# Schatten5.net
KiCad netlist of a schematic drawn in EAGLE
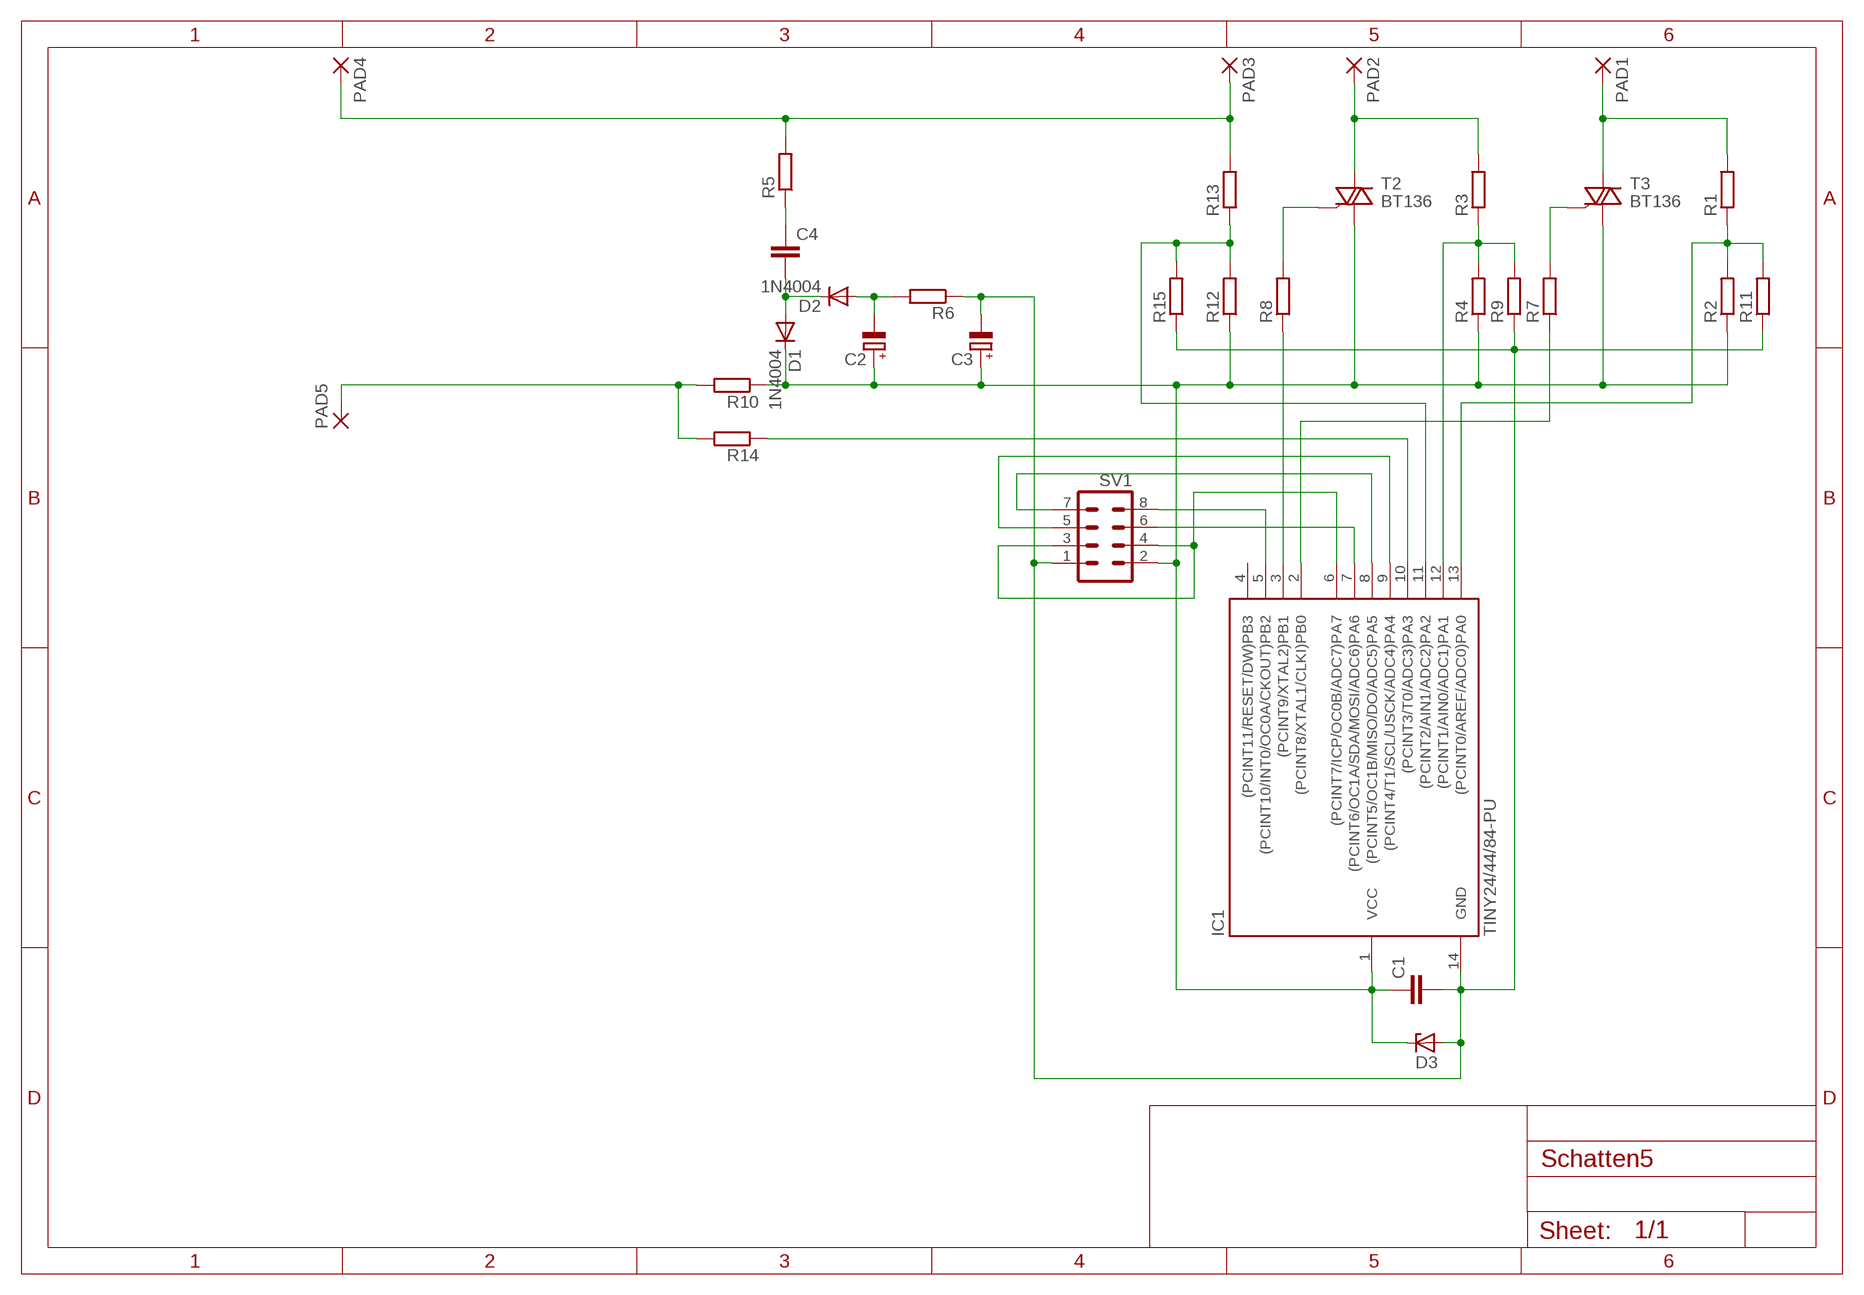
[diagram p0: schematic, sheet 1]

(export (version "E")
  (design (tool "Eeschema 10.0.6"))
  (components
    (comp (ref "C1")
      (value "C-EUC3225")
      (footprint "eagle-import:C3225")
      (libsource (lib "eagle-import") (part "C-EUC3225"))
    )
    (comp (ref "C2")
      (value "CPOL-EUE5-8.5")
      (footprint "eagle-import:E5-8,5")
      (libsource (lib "eagle-import") (part "CPOL-EUE5-8.5"))
    )
    (comp (ref "C3")
      (value "CPOL-EUE5-8.5")
      (footprint "eagle-import:E5-8,5")
      (libsource (lib "eagle-import") (part "CPOL-EUE5-8.5"))
    )
    (comp (ref "C4")
      (value "C-EU150-064X183")
      (footprint "eagle-import:C150-064X183")
      (libsource (lib "eagle-import") (part "C-EU150-064X183"))
    )
    (comp (ref "D1")
      (value "1N4004")
      (footprint "eagle-import:DO41-10")
      (libsource (lib "eagle-import") (part "1N4004"))
    )
    (comp (ref "D2")
      (value "1N4004")
      (footprint "eagle-import:DO41-10")
      (libsource (lib "eagle-import") (part "1N4004"))
    )
    (comp (ref "D3")
      (value "ZENER-DIODEZD-7.5")
      (footprint "eagle-import:ZDIO-7.5")
      (libsource (lib "eagle-import") (part "ZENER-DIODEZD-7.5"))
    )
    (comp (ref "IC1")
      (value "TINY24/44/84-PU")
      (footprint "eagle-import:DIL14")
      (libsource (lib "eagle-import") (part "TINY24/44/84-PU"))
    )
    (comp (ref "PAD1")
      (value "1,6/0,9")
      (footprint "eagle-import:1,6_0,9")
      (libsource (lib "eagle-import") (part "1,6/0,9"))
    )
    (comp (ref "PAD2")
      (value "1,6/0,9")
      (footprint "eagle-import:1,6_0,9")
      (libsource (lib "eagle-import") (part "1,6/0,9"))
    )
    (comp (ref "PAD3")
      (value "1,6/0,9")
      (footprint "eagle-import:1,6_0,9")
      (libsource (lib "eagle-import") (part "1,6/0,9"))
    )
    (comp (ref "PAD4")
      (value "1,6/0,9")
      (footprint "eagle-import:1,6_0,9")
      (libsource (lib "eagle-import") (part "1,6/0,9"))
    )
    (comp (ref "PAD5")
      (value "1,6/0,9")
      (footprint "eagle-import:1,6_0,9")
      (libsource (lib "eagle-import") (part "1,6/0,9"))
    )
    (comp (ref "R1")
      (value "R-EU_0207/10")
      (footprint "eagle-import:0207_10")
      (libsource (lib "eagle-import") (part "R-EU_0207/10"))
    )
    (comp (ref "R2")
      (value "R-EU_0207/10")
      (footprint "eagle-import:0207_10")
      (libsource (lib "eagle-import") (part "R-EU_0207/10"))
    )
    (comp (ref "R3")
      (value "R-EU_0207/10")
      (footprint "eagle-import:0207_10")
      (libsource (lib "eagle-import") (part "R-EU_0207/10"))
    )
    (comp (ref "R4")
      (value "R-EU_0207/10")
      (footprint "eagle-import:0207_10")
      (libsource (lib "eagle-import") (part "R-EU_0207/10"))
    )
    (comp (ref "R5")
      (value "R-EU_0207/10")
      (footprint "eagle-import:0207_10")
      (libsource (lib "eagle-import") (part "R-EU_0207/10"))
    )
    (comp (ref "R6")
      (value "R-EU_0207/10")
      (footprint "eagle-import:0207_10")
      (libsource (lib "eagle-import") (part "R-EU_0207/10"))
    )
    (comp (ref "R7")
      (value "R-EU_0207/10")
      (footprint "eagle-import:0207_10")
      (libsource (lib "eagle-import") (part "R-EU_0207/10"))
    )
    (comp (ref "R8")
      (value "R-EU_0207/10")
      (footprint "eagle-import:0207_10")
      (libsource (lib "eagle-import") (part "R-EU_0207/10"))
    )
    (comp (ref "R9")
      (value "R-EU_0207/10")
      (footprint "eagle-import:0207_10")
      (libsource (lib "eagle-import") (part "R-EU_0207/10"))
    )
    (comp (ref "R10")
      (value "R-EU_0207/10")
      (footprint "eagle-import:0207_10")
      (libsource (lib "eagle-import") (part "R-EU_0207/10"))
    )
    (comp (ref "R11")
      (value "R-EU_0207/10")
      (footprint "eagle-import:0207_10")
      (libsource (lib "eagle-import") (part "R-EU_0207/10"))
    )
    (comp (ref "R12")
      (value "R-EU_0207/10")
      (footprint "eagle-import:0207_10")
      (libsource (lib "eagle-import") (part "R-EU_0207/10"))
    )
    (comp (ref "R13")
      (value "R-EU_0207/10")
      (footprint "eagle-import:0207_10")
      (libsource (lib "eagle-import") (part "R-EU_0207/10"))
    )
    (comp (ref "R14")
      (value "R-EU_0207/10")
      (footprint "eagle-import:0207_10")
      (libsource (lib "eagle-import") (part "R-EU_0207/10"))
    )
    (comp (ref "R15")
      (value "R-EU_0207/10")
      (footprint "eagle-import:0207_10")
      (libsource (lib "eagle-import") (part "R-EU_0207/10"))
    )
    (comp (ref "SV1")
      (value "MA04-2")
      (footprint "eagle-import:MA04-2")
      (libsource (lib "eagle-import") (part "MA04-2"))
    )
    (comp (ref "T2")
      (value "BT136")
      (footprint "eagle-import:TO220AB")
      (libsource (lib "eagle-import") (part "BT136"))
    )
    (comp (ref "T3")
      (value "BT136")
      (footprint "eagle-import:TO220AB")
      (libsource (lib "eagle-import") (part "BT136"))
    )
  )
  (nets
    (net (code "1") (name "Net-(C2-Pad-)") (class "Default")
      (node (ref "C2") (pin "-") (pinfunction "-_-") (pintype "passive"))
      (node (ref "D2") (pin "A") (pinfunction "A_A") (pintype "passive"))
      (node (ref "R6") (pin "2") (pinfunction "2_2") (pintype "passive"))
    )
    (net (code "2") (name "Net-(C4-Pad1)") (class "Default")
      (node (ref "C4") (pin "1") (pinfunction "1_1") (pintype "passive"))
      (node (ref "R5") (pin "1") (pinfunction "1_1") (pintype "passive"))
    )
    (net (code "3") (name "Net-(C4-Pad2)") (class "Default")
      (node (ref "C4") (pin "2") (pinfunction "2_2") (pintype "passive"))
      (node (ref "D1") (pin "A") (pinfunction "A_A") (pintype "passive"))
      (node (ref "D2") (pin "C") (pinfunction "C_C") (pintype "passive"))
    )
    (net (code "4") (name "Net-(IC1-(PCINT0{slash}AREF{slash}ADC0)PA0)") (class "Default")
      (node (ref "IC1") (pin "13") (pinfunction "(PCINT0/AREF/ADC0)PA0_13") (pintype "bidirectional"))
      (node (ref "R1") (pin "1") (pinfunction "1_1") (pintype "passive"))
      (node (ref "R11") (pin "2") (pinfunction "2_2") (pintype "passive"))
      (node (ref "R2") (pin "2") (pinfunction "2_2") (pintype "passive"))
    )
    (net (code "5") (name "Net-(IC1-(PCINT1{slash}AIN0{slash}ADC1)PA1)") (class "Default")
      (node (ref "IC1") (pin "12") (pinfunction "(PCINT1/AIN0/ADC1)PA1_12") (pintype "bidirectional"))
      (node (ref "R3") (pin "1") (pinfunction "1_1") (pintype "passive"))
      (node (ref "R4") (pin "2") (pinfunction "2_2") (pintype "passive"))
      (node (ref "R9") (pin "2") (pinfunction "2_2") (pintype "passive"))
    )
    (net (code "6") (name "Net-(IC1-(PCINT2{slash}AIN1{slash}ADC2)PA2)") (class "Default")
      (node (ref "IC1") (pin "11") (pinfunction "(PCINT2/AIN1/ADC2)PA2_11") (pintype "bidirectional"))
      (node (ref "R12") (pin "2") (pinfunction "2_2") (pintype "passive"))
      (node (ref "R13") (pin "1") (pinfunction "1_1") (pintype "passive"))
      (node (ref "R15") (pin "2") (pinfunction "2_2") (pintype "passive"))
    )
    (net (code "7") (name "Net-(IC1-(PCINT3{slash}T0{slash}ADC3)PA3)") (class "Default")
      (node (ref "IC1") (pin "10") (pinfunction "(PCINT3/T0/ADC3)PA3_10") (pintype "bidirectional"))
      (node (ref "R14") (pin "1") (pinfunction "1_1") (pintype "passive"))
    )
    (net (code "8") (name "Net-(IC1-(PCINT4{slash}T1{slash}SCL{slash}USCK{slash}ADC4)PA4)") (class "Default")
      (node (ref "IC1") (pin "9") (pinfunction "(PCINT4/T1/SCL/USCK/ADC4)PA4_9") (pintype "bidirectional"))
      (node (ref "SV1") (pin "5") (pinfunction "5_5") (pintype "passive"))
    )
    (net (code "9") (name "Net-(IC1-(PCINT5{slash}OC1B{slash}MISO{slash}DO{slash}ADC5)PA5)") (class "Default")
      (node (ref "IC1") (pin "8") (pinfunction "(PCINT5/OC1B/MISO/DO/ADC5)PA5_8") (pintype "bidirectional"))
      (node (ref "SV1") (pin "7") (pinfunction "7_7") (pintype "passive"))
    )
    (net (code "10") (name "Net-(IC1-(PCINT6{slash}OC1A{slash}SDA{slash}MOSI{slash}ADC6)PA6)") (class "Default")
      (node (ref "IC1") (pin "7") (pinfunction "(PCINT6/OC1A/SDA/MOSI/ADC6)PA6_7") (pintype "bidirectional"))
      (node (ref "SV1") (pin "6") (pinfunction "6_6") (pintype "passive"))
    )
    (net (code "11") (name "Net-(IC1-(PCINT7{slash}ICP{slash}OC0B{slash}ADC7)PA7)") (class "Default")
      (node (ref "IC1") (pin "6") (pinfunction "(PCINT7/ICP/OC0B/ADC7)PA7_6") (pintype "bidirectional"))
      (node (ref "SV1") (pin "3") (pinfunction "3_3") (pintype "passive"))
      (node (ref "SV1") (pin "4") (pinfunction "4_4") (pintype "passive"))
    )
    (net (code "12") (name "Net-(IC1-(PCINT8{slash}XTAL1{slash}CLKI)PB0)") (class "Default")
      (node (ref "IC1") (pin "2") (pinfunction "(PCINT8/XTAL1/CLKI)PB0_2") (pintype "bidirectional"))
      (node (ref "R7") (pin "1") (pinfunction "1_1") (pintype "passive"))
    )
    (net (code "13") (name "Net-(IC1-(PCINT9{slash}XTAL2)PB1)") (class "Default")
      (node (ref "IC1") (pin "3") (pinfunction "(PCINT9/XTAL2)PB1_3") (pintype "bidirectional"))
      (node (ref "R8") (pin "1") (pinfunction "1_1") (pintype "passive"))
    )
    (net (code "14") (name "Net-(IC1-(PCINT10{slash}INT0{slash}OC0A{slash}CKOUT)PB2)") (class "Default")
      (node (ref "IC1") (pin "5") (pinfunction "(PCINT10/INT0/OC0A/CKOUT)PB2_5") (pintype "bidirectional"))
      (node (ref "SV1") (pin "8") (pinfunction "8_8") (pintype "passive"))
    )
    (net (code "15") (name "Net-(IC1-GND)") (class "Default")
      (node (ref "C1") (pin "2") (pinfunction "2_2") (pintype "passive"))
      (node (ref "C3") (pin "-") (pinfunction "-_-") (pintype "passive"))
      (node (ref "D3") (pin "A") (pinfunction "A_A") (pintype "passive"))
      (node (ref "IC1") (pin "14") (pinfunction "GND_14") (pintype "power_in"))
      (node (ref "R11") (pin "1") (pinfunction "1_1") (pintype "passive"))
      (node (ref "R15") (pin "1") (pinfunction "1_1") (pintype "passive"))
      (node (ref "R6") (pin "1") (pinfunction "1_1") (pintype "passive"))
      (node (ref "R9") (pin "1") (pinfunction "1_1") (pintype "passive"))
      (node (ref "SV1") (pin "1") (pinfunction "1_1") (pintype "passive"))
    )
    (net (code "16") (name "Net-(IC1-VCC)") (class "Default")
      (node (ref "C1") (pin "1") (pinfunction "1_1") (pintype "passive"))
      (node (ref "C2") (pin "+") (pinfunction "+_+") (pintype "passive"))
      (node (ref "C3") (pin "+") (pinfunction "+_+") (pintype "passive"))
      (node (ref "D1") (pin "C") (pinfunction "C_C") (pintype "passive"))
      (node (ref "D3") (pin "C") (pinfunction "C_C") (pintype "passive"))
      (node (ref "IC1") (pin "1") (pinfunction "VCC_1") (pintype "power_in"))
      (node (ref "R10") (pin "1") (pinfunction "1_1") (pintype "passive"))
      (node (ref "R12") (pin "1") (pinfunction "1_1") (pintype "passive"))
      (node (ref "R2") (pin "1") (pinfunction "1_1") (pintype "passive"))
      (node (ref "R4") (pin "1") (pinfunction "1_1") (pintype "passive"))
      (node (ref "SV1") (pin "2") (pinfunction "2_2") (pintype "passive"))
      (node (ref "T2") (pin "1") (pinfunction "A1_1") (pintype "passive"))
      (node (ref "T3") (pin "1") (pinfunction "A1_1") (pintype "passive"))
    )
    (net (code "17") (name "Net-(PAD1-P)") (class "Default")
      (node (ref "PAD1") (pin "1") (pinfunction "P_1") (pintype "passive"))
      (node (ref "R1") (pin "2") (pinfunction "2_2") (pintype "passive"))
      (node (ref "T3") (pin "2") (pinfunction "A2_2") (pintype "passive"))
    )
    (net (code "18") (name "Net-(PAD2-P)") (class "Default")
      (node (ref "PAD2") (pin "1") (pinfunction "P_1") (pintype "passive"))
      (node (ref "R3") (pin "2") (pinfunction "2_2") (pintype "passive"))
      (node (ref "T2") (pin "2") (pinfunction "A2_2") (pintype "passive"))
    )
    (net (code "19") (name "Net-(PAD3-P)") (class "Default")
      (node (ref "PAD3") (pin "1") (pinfunction "P_1") (pintype "passive"))
      (node (ref "PAD4") (pin "1") (pinfunction "P_1") (pintype "passive"))
      (node (ref "R13") (pin "2") (pinfunction "2_2") (pintype "passive"))
      (node (ref "R5") (pin "2") (pinfunction "2_2") (pintype "passive"))
    )
    (net (code "20") (name "Net-(PAD5-P)") (class "Default")
      (node (ref "PAD5") (pin "1") (pinfunction "P_1") (pintype "passive"))
      (node (ref "R10") (pin "2") (pinfunction "2_2") (pintype "passive"))
      (node (ref "R14") (pin "2") (pinfunction "2_2") (pintype "passive"))
    )
    (net (code "21") (name "Net-(T2-G)") (class "Default")
      (node (ref "R8") (pin "2") (pinfunction "2_2") (pintype "passive"))
      (node (ref "T2") (pin "3") (pinfunction "G_3") (pintype "passive"))
    )
    (net (code "22") (name "Net-(T3-G)") (class "Default")
      (node (ref "R7") (pin "2") (pinfunction "2_2") (pintype "passive"))
      (node (ref "T3") (pin "3") (pinfunction "G_3") (pintype "passive"))
    )
    (net (code "23") (name "unconnected-(IC1-(PCINT11{slash}RESET{slash}DW)PB3-Pad4)") (class "Default")
      (node (ref "IC1") (pin "4") (pinfunction "(PCINT11/RESET/DW)PB3_4") (pintype "bidirectional"))
    )
  )
)
